# LightWand_KosmonautED.net
KiCad netlist of a schematic drawn in EAGLE
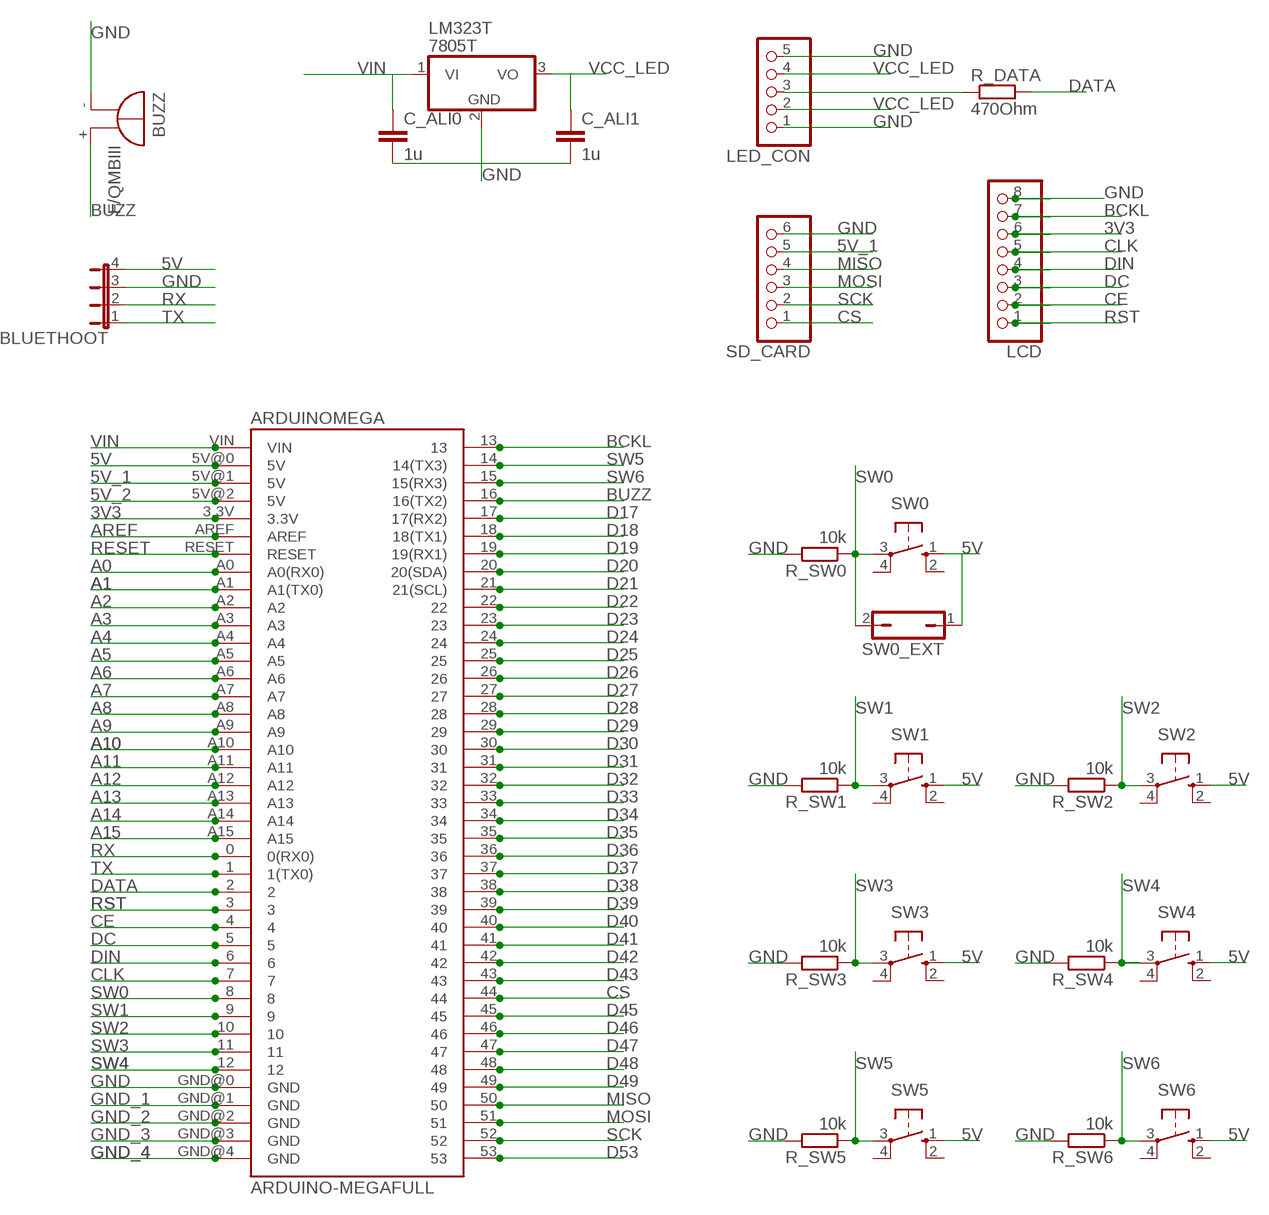
[diagram p0: schematic, sheet 1]

(export (version "E")
  (design (tool "Eeschema 10.0.6"))
  (components
    (comp (ref "ARDUINOMEGA")
      (value "ARDUINO-MEGAFULL")
      (footprint "eagle-import:ARDUINO_MEGA")
      (libsource (lib "eagle-import") (part "ARDUINO-MEGAFULL"))
    )
    (comp (ref "BLUETHOOT")
      (value "JP4E")
      (footprint "eagle-import:JP4")
      (libsource (lib "eagle-import") (part "JP4E"))
    )
    (comp (ref "BUZZ")
      (value "F/QMBIII")
      (footprint "eagle-import:F_QMBIII")
      (libsource (lib "eagle-import") (part "F/QMBIII"))
    )
    (comp (ref "C_ALI0")
      (value "1u")
      (footprint "eagle-import:C1206")
      (libsource (lib "eagle-import") (part "C-EUC1206"))
    )
    (comp (ref "C_ALI1")
      (value "1u")
      (footprint "eagle-import:C1206")
      (libsource (lib "eagle-import") (part "C-EUC1206"))
    )
    (comp (ref "LCD")
      (value "PINHD-1X8")
      (footprint "eagle-import:1X08")
      (libsource (lib "eagle-import") (part "PINHD-1X8"))
    )
    (comp (ref "LED_CON")
      (value "PINHD-1X5")
      (footprint "eagle-import:1X05")
      (libsource (lib "eagle-import") (part "PINHD-1X5"))
    )
    (comp (ref "LM323T")
      (value "7805T")
      (footprint "eagle-import:TO220H")
      (libsource (lib "eagle-import") (part "78T05"))
    )
    (comp (ref "R_DATA")
      (value "470Ohm")
      (footprint "eagle-import:R1206")
      (libsource (lib "eagle-import") (part "R-EU_R1206"))
    )
    (comp (ref "R_SW0")
      (value "10k")
      (footprint "eagle-import:R1206")
      (libsource (lib "eagle-import") (part "R-EU_R1206"))
    )
    (comp (ref "R_SW1")
      (value "10k")
      (footprint "eagle-import:R1206")
      (libsource (lib "eagle-import") (part "R-EU_R1206"))
    )
    (comp (ref "R_SW2")
      (value "10k")
      (footprint "eagle-import:R1206")
      (libsource (lib "eagle-import") (part "R-EU_R1206"))
    )
    (comp (ref "R_SW3")
      (value "10k")
      (footprint "eagle-import:R1206")
      (libsource (lib "eagle-import") (part "R-EU_R1206"))
    )
    (comp (ref "R_SW4")
      (value "10k")
      (footprint "eagle-import:R1206")
      (libsource (lib "eagle-import") (part "R-EU_R1206"))
    )
    (comp (ref "R_SW5")
      (value "10k")
      (footprint "eagle-import:R1206")
      (libsource (lib "eagle-import") (part "R-EU_R1206"))
    )
    (comp (ref "R_SW6")
      (value "10k")
      (footprint "eagle-import:R1206")
      (libsource (lib "eagle-import") (part "R-EU_R1206"))
    )
    (comp (ref "SD_CARD")
      (value "PINHD-1X6")
      (footprint "eagle-import:1X06")
      (libsource (lib "eagle-import") (part "PINHD-1X6"))
    )
    (comp (ref "SW0")
      (value "10-XX")
      (footprint "eagle-import:B3F-10XX")
      (fields (field (name "MPN") "B3F-1000"))
      (libsource (lib "eagle-import") (part "10-XX"))
    )
    (comp (ref "SW0_EXT")
      (value "JP1Q")
      (footprint "eagle-import:JP1")
      (libsource (lib "eagle-import") (part "JP1Q"))
    )
    (comp (ref "SW1")
      (value "10-XX")
      (footprint "eagle-import:B3F-10XX")
      (fields (field (name "MPN") "B3F-1000"))
      (libsource (lib "eagle-import") (part "10-XX"))
    )
    (comp (ref "SW2")
      (value "10-XX")
      (footprint "eagle-import:B3F-10XX")
      (fields (field (name "MPN") "B3F-1000"))
      (libsource (lib "eagle-import") (part "10-XX"))
    )
    (comp (ref "SW3")
      (value "10-XX")
      (footprint "eagle-import:B3F-10XX")
      (fields (field (name "MPN") "B3F-1000"))
      (libsource (lib "eagle-import") (part "10-XX"))
    )
    (comp (ref "SW4")
      (value "10-XX")
      (footprint "eagle-import:B3F-10XX")
      (fields (field (name "MPN") "B3F-1000"))
      (libsource (lib "eagle-import") (part "10-XX"))
    )
    (comp (ref "SW5")
      (value "10-XX")
      (footprint "eagle-import:B3F-10XX")
      (fields (field (name "MPN") "B3F-1000"))
      (libsource (lib "eagle-import") (part "10-XX"))
    )
    (comp (ref "SW6")
      (value "10-XX")
      (footprint "eagle-import:B3F-10XX")
      (fields (field (name "MPN") "B3F-1000"))
      (libsource (lib "eagle-import") (part "10-XX"))
    )
  )
  (nets
    (net (code "1") (name "/3V3") (class "Default")
      (node (ref "ARDUINOMEGA") (pin "3.3V") (pinfunction "3.3V_3.3V") (pintype "bidirectional"))
      (node (ref "LCD") (pin "6") (pinfunction "6_6") (pintype "passive"))
    )
    (net (code "2") (name "/5V") (class "Default")
      (node (ref "ARDUINOMEGA") (pin "5V@0") (pinfunction "5V_5V@0") (pintype "bidirectional"))
      (node (ref "BLUETHOOT") (pin "4") (pinfunction "4_4") (pintype "passive"))
      (node (ref "SW0") (pin "1") (pinfunction "S_1") (pintype "passive"))
      (node (ref "SW0_EXT") (pin "1") (pinfunction "1_1") (pintype "passive"))
      (node (ref "SW1") (pin "1") (pinfunction "S_1") (pintype "passive"))
      (node (ref "SW2") (pin "1") (pinfunction "S_1") (pintype "passive"))
      (node (ref "SW3") (pin "1") (pinfunction "S_1") (pintype "passive"))
      (node (ref "SW4") (pin "1") (pinfunction "S_1") (pintype "passive"))
      (node (ref "SW5") (pin "1") (pinfunction "S_1") (pintype "passive"))
      (node (ref "SW6") (pin "1") (pinfunction "S_1") (pintype "passive"))
    )
    (net (code "3") (name "/5V_1") (class "Default")
      (node (ref "ARDUINOMEGA") (pin "5V@1") (pinfunction "5V_5V@1") (pintype "bidirectional"))
      (node (ref "SD_CARD") (pin "5") (pinfunction "5_5") (pintype "passive"))
    )
    (net (code "4") (name "/5V_2") (class "Default")
      (node (ref "ARDUINOMEGA") (pin "5V@2") (pinfunction "5V_5V@2") (pintype "bidirectional"))
    )
    (net (code "5") (name "/A0") (class "Default")
      (node (ref "ARDUINOMEGA") (pin "A0") (pinfunction "A0(RX0)_A0") (pintype "bidirectional"))
    )
    (net (code "6") (name "/A1") (class "Default")
      (node (ref "ARDUINOMEGA") (pin "A1") (pinfunction "A1(TX0)_A1") (pintype "bidirectional"))
    )
    (net (code "7") (name "/A2") (class "Default")
      (node (ref "ARDUINOMEGA") (pin "A2") (pinfunction "A2_A2") (pintype "bidirectional"))
    )
    (net (code "8") (name "/A3") (class "Default")
      (node (ref "ARDUINOMEGA") (pin "A3") (pinfunction "A3_A3") (pintype "bidirectional"))
    )
    (net (code "9") (name "/A4") (class "Default")
      (node (ref "ARDUINOMEGA") (pin "A4") (pinfunction "A4_A4") (pintype "bidirectional"))
    )
    (net (code "10") (name "/A5") (class "Default")
      (node (ref "ARDUINOMEGA") (pin "A5") (pinfunction "A5_A5") (pintype "bidirectional"))
    )
    (net (code "11") (name "/A6") (class "Default")
      (node (ref "ARDUINOMEGA") (pin "A6") (pinfunction "A6_A6") (pintype "bidirectional"))
    )
    (net (code "12") (name "/A7") (class "Default")
      (node (ref "ARDUINOMEGA") (pin "A7") (pinfunction "A7_A7") (pintype "bidirectional"))
    )
    (net (code "13") (name "/A8") (class "Default")
      (node (ref "ARDUINOMEGA") (pin "A8") (pinfunction "A8_A8") (pintype "bidirectional"))
    )
    (net (code "14") (name "/A9") (class "Default")
      (node (ref "ARDUINOMEGA") (pin "A9") (pinfunction "A9_A9") (pintype "bidirectional"))
    )
    (net (code "15") (name "/A10") (class "Default")
      (node (ref "ARDUINOMEGA") (pin "A10") (pinfunction "A10_A10") (pintype "bidirectional"))
    )
    (net (code "16") (name "/A11") (class "Default")
      (node (ref "ARDUINOMEGA") (pin "A11") (pinfunction "A11_A11") (pintype "bidirectional"))
    )
    (net (code "17") (name "/A12") (class "Default")
      (node (ref "ARDUINOMEGA") (pin "A12") (pinfunction "A12_A12") (pintype "bidirectional"))
    )
    (net (code "18") (name "/A13") (class "Default")
      (node (ref "ARDUINOMEGA") (pin "A13") (pinfunction "A13_A13") (pintype "bidirectional"))
    )
    (net (code "19") (name "/A14") (class "Default")
      (node (ref "ARDUINOMEGA") (pin "A14") (pinfunction "A14_A14") (pintype "bidirectional"))
    )
    (net (code "20") (name "/A15") (class "Default")
      (node (ref "ARDUINOMEGA") (pin "A15") (pinfunction "A15_A15") (pintype "bidirectional"))
    )
    (net (code "21") (name "/AREF") (class "Default")
      (node (ref "ARDUINOMEGA") (pin "AREF") (pinfunction "AREF_AREF") (pintype "bidirectional"))
    )
    (net (code "22") (name "/BCKL") (class "Default")
      (node (ref "ARDUINOMEGA") (pin "13") (pinfunction "13_13") (pintype "bidirectional"))
      (node (ref "LCD") (pin "7") (pinfunction "7_7") (pintype "passive"))
    )
    (net (code "23") (name "/BUZZ") (class "Default")
      (node (ref "ARDUINOMEGA") (pin "16") (pinfunction "16(TX2)_16") (pintype "bidirectional"))
      (node (ref "BUZZ") (pin "+") (pinfunction "-_+") (pintype "passive"))
    )
    (net (code "24") (name "/CE") (class "Default")
      (node (ref "ARDUINOMEGA") (pin "4") (pinfunction "4_4") (pintype "bidirectional"))
      (node (ref "LCD") (pin "2") (pinfunction "2_2") (pintype "passive"))
    )
    (net (code "25") (name "/CLK") (class "Default")
      (node (ref "ARDUINOMEGA") (pin "7") (pinfunction "7_7") (pintype "bidirectional"))
      (node (ref "LCD") (pin "5") (pinfunction "5_5") (pintype "passive"))
    )
    (net (code "26") (name "/CS") (class "Default")
      (node (ref "ARDUINOMEGA") (pin "44") (pinfunction "44_44") (pintype "bidirectional"))
      (node (ref "SD_CARD") (pin "1") (pinfunction "1_1") (pintype "passive"))
    )
    (net (code "27") (name "/D17") (class "Default")
      (node (ref "ARDUINOMEGA") (pin "17") (pinfunction "17(RX2)_17") (pintype "bidirectional"))
    )
    (net (code "28") (name "/D18") (class "Default")
      (node (ref "ARDUINOMEGA") (pin "18") (pinfunction "18(TX1)_18") (pintype "bidirectional"))
    )
    (net (code "29") (name "/D19") (class "Default")
      (node (ref "ARDUINOMEGA") (pin "19") (pinfunction "19(RX1)_19") (pintype "bidirectional"))
    )
    (net (code "30") (name "/D20") (class "Default")
      (node (ref "ARDUINOMEGA") (pin "20") (pinfunction "20(SDA)_20") (pintype "bidirectional"))
    )
    (net (code "31") (name "/D21") (class "Default")
      (node (ref "ARDUINOMEGA") (pin "21") (pinfunction "21(SCL)_21") (pintype "bidirectional"))
    )
    (net (code "32") (name "/D22") (class "Default")
      (node (ref "ARDUINOMEGA") (pin "22") (pinfunction "22_22") (pintype "bidirectional"))
    )
    (net (code "33") (name "/D23") (class "Default")
      (node (ref "ARDUINOMEGA") (pin "23") (pinfunction "23_23") (pintype "bidirectional"))
    )
    (net (code "34") (name "/D24") (class "Default")
      (node (ref "ARDUINOMEGA") (pin "24") (pinfunction "24_24") (pintype "bidirectional"))
    )
    (net (code "35") (name "/D25") (class "Default")
      (node (ref "ARDUINOMEGA") (pin "25") (pinfunction "25_25") (pintype "bidirectional"))
    )
    (net (code "36") (name "/D26") (class "Default")
      (node (ref "ARDUINOMEGA") (pin "26") (pinfunction "26_26") (pintype "bidirectional"))
    )
    (net (code "37") (name "/D27") (class "Default")
      (node (ref "ARDUINOMEGA") (pin "27") (pinfunction "27_27") (pintype "bidirectional"))
    )
    (net (code "38") (name "/D28") (class "Default")
      (node (ref "ARDUINOMEGA") (pin "28") (pinfunction "28_28") (pintype "bidirectional"))
    )
    (net (code "39") (name "/D29") (class "Default")
      (node (ref "ARDUINOMEGA") (pin "29") (pinfunction "29_29") (pintype "bidirectional"))
    )
    (net (code "40") (name "/D30") (class "Default")
      (node (ref "ARDUINOMEGA") (pin "30") (pinfunction "30_30") (pintype "bidirectional"))
    )
    (net (code "41") (name "/D31") (class "Default")
      (node (ref "ARDUINOMEGA") (pin "31") (pinfunction "31_31") (pintype "bidirectional"))
    )
    (net (code "42") (name "/D32") (class "Default")
      (node (ref "ARDUINOMEGA") (pin "32") (pinfunction "32_32") (pintype "bidirectional"))
    )
    (net (code "43") (name "/D33") (class "Default")
      (node (ref "ARDUINOMEGA") (pin "33") (pinfunction "33_33") (pintype "bidirectional"))
    )
    (net (code "44") (name "/D34") (class "Default")
      (node (ref "ARDUINOMEGA") (pin "34") (pinfunction "34_34") (pintype "bidirectional"))
    )
    (net (code "45") (name "/D35") (class "Default")
      (node (ref "ARDUINOMEGA") (pin "35") (pinfunction "35_35") (pintype "bidirectional"))
    )
    (net (code "46") (name "/D36") (class "Default")
      (node (ref "ARDUINOMEGA") (pin "36") (pinfunction "36_36") (pintype "bidirectional"))
    )
    (net (code "47") (name "/D37") (class "Default")
      (node (ref "ARDUINOMEGA") (pin "37") (pinfunction "37_37") (pintype "bidirectional"))
    )
    (net (code "48") (name "/D38") (class "Default")
      (node (ref "ARDUINOMEGA") (pin "38") (pinfunction "38_38") (pintype "bidirectional"))
    )
    (net (code "49") (name "/D39") (class "Default")
      (node (ref "ARDUINOMEGA") (pin "39") (pinfunction "39_39") (pintype "bidirectional"))
    )
    (net (code "50") (name "/D40") (class "Default")
      (node (ref "ARDUINOMEGA") (pin "40") (pinfunction "40_40") (pintype "bidirectional"))
    )
    (net (code "51") (name "/D41") (class "Default")
      (node (ref "ARDUINOMEGA") (pin "41") (pinfunction "41_41") (pintype "bidirectional"))
    )
    (net (code "52") (name "/D42") (class "Default")
      (node (ref "ARDUINOMEGA") (pin "42") (pinfunction "42_42") (pintype "bidirectional"))
    )
    (net (code "53") (name "/D43") (class "Default")
      (node (ref "ARDUINOMEGA") (pin "43") (pinfunction "43_43") (pintype "bidirectional"))
    )
    (net (code "54") (name "/D45") (class "Default")
      (node (ref "ARDUINOMEGA") (pin "45") (pinfunction "45_45") (pintype "bidirectional"))
    )
    (net (code "55") (name "/D46") (class "Default")
      (node (ref "ARDUINOMEGA") (pin "46") (pinfunction "46_46") (pintype "bidirectional"))
    )
    (net (code "56") (name "/D47") (class "Default")
      (node (ref "ARDUINOMEGA") (pin "47") (pinfunction "47_47") (pintype "bidirectional"))
    )
    (net (code "57") (name "/D48") (class "Default")
      (node (ref "ARDUINOMEGA") (pin "48") (pinfunction "48_48") (pintype "bidirectional"))
    )
    (net (code "58") (name "/D49") (class "Default")
      (node (ref "ARDUINOMEGA") (pin "49") (pinfunction "49_49") (pintype "bidirectional"))
    )
    (net (code "59") (name "/D53") (class "Default")
      (node (ref "ARDUINOMEGA") (pin "53") (pinfunction "53_53") (pintype "bidirectional"))
    )
    (net (code "60") (name "/DATA") (class "Default")
      (node (ref "ARDUINOMEGA") (pin "2") (pinfunction "2_2") (pintype "bidirectional"))
      (node (ref "R_DATA") (pin "2") (pinfunction "2_2") (pintype "passive"))
    )
    (net (code "61") (name "/DC") (class "Default")
      (node (ref "ARDUINOMEGA") (pin "5") (pinfunction "5_5") (pintype "bidirectional"))
      (node (ref "LCD") (pin "3") (pinfunction "3_3") (pintype "passive"))
    )
    (net (code "62") (name "/DIN") (class "Default")
      (node (ref "ARDUINOMEGA") (pin "6") (pinfunction "6_6") (pintype "bidirectional"))
      (node (ref "LCD") (pin "4") (pinfunction "4_4") (pintype "passive"))
    )
    (net (code "63") (name "/GND") (class "Default")
      (node (ref "ARDUINOMEGA") (pin "GND@0") (pinfunction "GND_GND@0") (pintype "bidirectional"))
      (node (ref "BLUETHOOT") (pin "3") (pinfunction "3_3") (pintype "passive"))
      (node (ref "BUZZ") (pin "-") (pinfunction "+_-") (pintype "passive"))
      (node (ref "C_ALI0") (pin "2") (pinfunction "2_2") (pintype "passive"))
      (node (ref "C_ALI1") (pin "2") (pinfunction "2_2") (pintype "passive"))
      (node (ref "LCD") (pin "8") (pinfunction "8_8") (pintype "passive"))
      (node (ref "LED_CON") (pin "1") (pinfunction "1_1") (pintype "passive"))
      (node (ref "LED_CON") (pin "5") (pinfunction "5_5") (pintype "passive"))
      (node (ref "LM323T") (pin "2") (pinfunction "GND_2") (pintype "passive"))
      (node (ref "R_SW0") (pin "2") (pinfunction "2_2") (pintype "passive"))
      (node (ref "R_SW1") (pin "2") (pinfunction "2_2") (pintype "passive"))
      (node (ref "R_SW2") (pin "2") (pinfunction "2_2") (pintype "passive"))
      (node (ref "R_SW3") (pin "2") (pinfunction "2_2") (pintype "passive"))
      (node (ref "R_SW4") (pin "2") (pinfunction "2_2") (pintype "passive"))
      (node (ref "R_SW5") (pin "2") (pinfunction "2_2") (pintype "passive"))
      (node (ref "R_SW6") (pin "2") (pinfunction "2_2") (pintype "passive"))
      (node (ref "SD_CARD") (pin "6") (pinfunction "6_6") (pintype "passive"))
    )
    (net (code "64") (name "/GND_1") (class "Default")
      (node (ref "ARDUINOMEGA") (pin "GND@1") (pinfunction "GND_GND@1") (pintype "bidirectional"))
    )
    (net (code "65") (name "/GND_2") (class "Default")
      (node (ref "ARDUINOMEGA") (pin "GND@2") (pinfunction "GND_GND@2") (pintype "bidirectional"))
    )
    (net (code "66") (name "/GND_3") (class "Default")
      (node (ref "ARDUINOMEGA") (pin "GND@3") (pinfunction "GND_GND@3") (pintype "bidirectional"))
    )
    (net (code "67") (name "/GND_4") (class "Default")
      (node (ref "ARDUINOMEGA") (pin "GND@4") (pinfunction "GND_GND@4") (pintype "bidirectional"))
    )
    (net (code "68") (name "/MISO") (class "Default")
      (node (ref "ARDUINOMEGA") (pin "50") (pinfunction "50_50") (pintype "bidirectional"))
      (node (ref "SD_CARD") (pin "4") (pinfunction "4_4") (pintype "passive"))
    )
    (net (code "69") (name "/MOSI") (class "Default")
      (node (ref "ARDUINOMEGA") (pin "51") (pinfunction "51_51") (pintype "bidirectional"))
      (node (ref "SD_CARD") (pin "3") (pinfunction "3_3") (pintype "passive"))
    )
    (net (code "70") (name "/RESET") (class "Default")
      (node (ref "ARDUINOMEGA") (pin "RESET") (pinfunction "RESET_RESET") (pintype "bidirectional"))
    )
    (net (code "71") (name "/RST") (class "Default")
      (node (ref "ARDUINOMEGA") (pin "3") (pinfunction "3_3") (pintype "bidirectional"))
      (node (ref "LCD") (pin "1") (pinfunction "1_1") (pintype "passive"))
    )
    (net (code "72") (name "/RX") (class "Default")
      (node (ref "ARDUINOMEGA") (pin "0") (pinfunction "0(RX0)_0") (pintype "bidirectional"))
      (node (ref "BLUETHOOT") (pin "2") (pinfunction "2_2") (pintype "passive"))
    )
    (net (code "73") (name "/SCK") (class "Default")
      (node (ref "ARDUINOMEGA") (pin "52") (pinfunction "52_52") (pintype "bidirectional"))
      (node (ref "SD_CARD") (pin "2") (pinfunction "2_2") (pintype "passive"))
    )
    (net (code "74") (name "/SW0") (class "Default")
      (node (ref "ARDUINOMEGA") (pin "8") (pinfunction "8_8") (pintype "bidirectional"))
      (node (ref "R_SW0") (pin "1") (pinfunction "1_1") (pintype "passive"))
      (node (ref "SW0") (pin "3") (pinfunction "P_3") (pintype "passive"))
      (node (ref "SW0_EXT") (pin "2") (pinfunction "2_2") (pintype "passive"))
    )
    (net (code "75") (name "/SW1") (class "Default")
      (node (ref "ARDUINOMEGA") (pin "9") (pinfunction "9_9") (pintype "bidirectional"))
      (node (ref "R_SW1") (pin "1") (pinfunction "1_1") (pintype "passive"))
      (node (ref "SW1") (pin "3") (pinfunction "P_3") (pintype "passive"))
    )
    (net (code "76") (name "/SW2") (class "Default")
      (node (ref "ARDUINOMEGA") (pin "10") (pinfunction "10_10") (pintype "bidirectional"))
      (node (ref "R_SW2") (pin "1") (pinfunction "1_1") (pintype "passive"))
      (node (ref "SW2") (pin "3") (pinfunction "P_3") (pintype "passive"))
    )
    (net (code "77") (name "/SW3") (class "Default")
      (node (ref "ARDUINOMEGA") (pin "11") (pinfunction "11_11") (pintype "bidirectional"))
      (node (ref "R_SW3") (pin "1") (pinfunction "1_1") (pintype "passive"))
      (node (ref "SW3") (pin "3") (pinfunction "P_3") (pintype "passive"))
    )
    (net (code "78") (name "/SW4") (class "Default")
      (node (ref "ARDUINOMEGA") (pin "12") (pinfunction "12_12") (pintype "bidirectional"))
      (node (ref "R_SW4") (pin "1") (pinfunction "1_1") (pintype "passive"))
      (node (ref "SW4") (pin "3") (pinfunction "P_3") (pintype "passive"))
    )
    (net (code "79") (name "/SW5") (class "Default")
      (node (ref "ARDUINOMEGA") (pin "14") (pinfunction "14(TX3)_14") (pintype "bidirectional"))
      (node (ref "R_SW5") (pin "1") (pinfunction "1_1") (pintype "passive"))
      (node (ref "SW5") (pin "3") (pinfunction "P_3") (pintype "passive"))
    )
    (net (code "80") (name "/SW6") (class "Default")
      (node (ref "ARDUINOMEGA") (pin "15") (pinfunction "15(RX3)_15") (pintype "bidirectional"))
      (node (ref "R_SW6") (pin "1") (pinfunction "1_1") (pintype "passive"))
      (node (ref "SW6") (pin "3") (pinfunction "P_3") (pintype "passive"))
    )
    (net (code "81") (name "/TX") (class "Default")
      (node (ref "ARDUINOMEGA") (pin "1") (pinfunction "1(TX0)_1") (pintype "bidirectional"))
      (node (ref "BLUETHOOT") (pin "1") (pinfunction "1_1") (pintype "passive"))
    )
    (net (code "82") (name "/VCC_LED") (class "Default")
      (node (ref "C_ALI1") (pin "1") (pinfunction "1_1") (pintype "passive"))
      (node (ref "LED_CON") (pin "2") (pinfunction "2_2") (pintype "passive"))
      (node (ref "LED_CON") (pin "4") (pinfunction "4_4") (pintype "passive"))
      (node (ref "LM323T") (pin "3") (pinfunction "VO_3") (pintype "passive"))
    )
    (net (code "83") (name "/VIN") (class "Default")
      (node (ref "ARDUINOMEGA") (pin "VIN") (pinfunction "VIN_VIN") (pintype "bidirectional"))
      (node (ref "C_ALI0") (pin "1") (pinfunction "1_1") (pintype "passive"))
      (node (ref "LM323T") (pin "1") (pinfunction "VI_1") (pintype "input"))
    )
    (net (code "84") (name "Net-(LED_CON-Pad3)") (class "Default")
      (node (ref "LED_CON") (pin "3") (pinfunction "3_3") (pintype "passive"))
      (node (ref "R_DATA") (pin "1") (pinfunction "1_1") (pintype "passive"))
    )
    (net (code "85") (name "unconnected-(SW0-P1-Pad4)") (class "Default")
      (node (ref "SW0") (pin "4") (pinfunction "P1_4") (pintype "passive"))
    )
    (net (code "86") (name "unconnected-(SW0-S1-Pad2)") (class "Default")
      (node (ref "SW0") (pin "2") (pinfunction "S1_2") (pintype "passive"))
    )
    (net (code "87") (name "unconnected-(SW1-P1-Pad4)") (class "Default")
      (node (ref "SW1") (pin "4") (pinfunction "P1_4") (pintype "passive"))
    )
    (net (code "88") (name "unconnected-(SW1-S1-Pad2)") (class "Default")
      (node (ref "SW1") (pin "2") (pinfunction "S1_2") (pintype "passive"))
    )
    (net (code "89") (name "unconnected-(SW2-P1-Pad4)") (class "Default")
      (node (ref "SW2") (pin "4") (pinfunction "P1_4") (pintype "passive"))
    )
    (net (code "90") (name "unconnected-(SW2-S1-Pad2)") (class "Default")
      (node (ref "SW2") (pin "2") (pinfunction "S1_2") (pintype "passive"))
    )
    (net (code "91") (name "unconnected-(SW3-P1-Pad4)") (class "Default")
      (node (ref "SW3") (pin "4") (pinfunction "P1_4") (pintype "passive"))
    )
    (net (code "92") (name "unconnected-(SW3-S1-Pad2)") (class "Default")
      (node (ref "SW3") (pin "2") (pinfunction "S1_2") (pintype "passive"))
    )
    (net (code "93") (name "unconnected-(SW4-P1-Pad4)") (class "Default")
      (node (ref "SW4") (pin "4") (pinfunction "P1_4") (pintype "passive"))
    )
    (net (code "94") (name "unconnected-(SW4-S1-Pad2)") (class "Default")
      (node (ref "SW4") (pin "2") (pinfunction "S1_2") (pintype "passive"))
    )
    (net (code "95") (name "unconnected-(SW5-P1-Pad4)") (class "Default")
      (node (ref "SW5") (pin "4") (pinfunction "P1_4") (pintype "passive"))
    )
    (net (code "96") (name "unconnected-(SW5-S1-Pad2)") (class "Default")
      (node (ref "SW5") (pin "2") (pinfunction "S1_2") (pintype "passive"))
    )
    (net (code "97") (name "unconnected-(SW6-P1-Pad4)") (class "Default")
      (node (ref "SW6") (pin "4") (pinfunction "P1_4") (pintype "passive"))
    )
    (net (code "98") (name "unconnected-(SW6-S1-Pad2)") (class "Default")
      (node (ref "SW6") (pin "2") (pinfunction "S1_2") (pintype "passive"))
    )
  )
)
